# pca20054_sheet4_power_control.net
KiCad netlist of a schematic drawn in Altium Designer
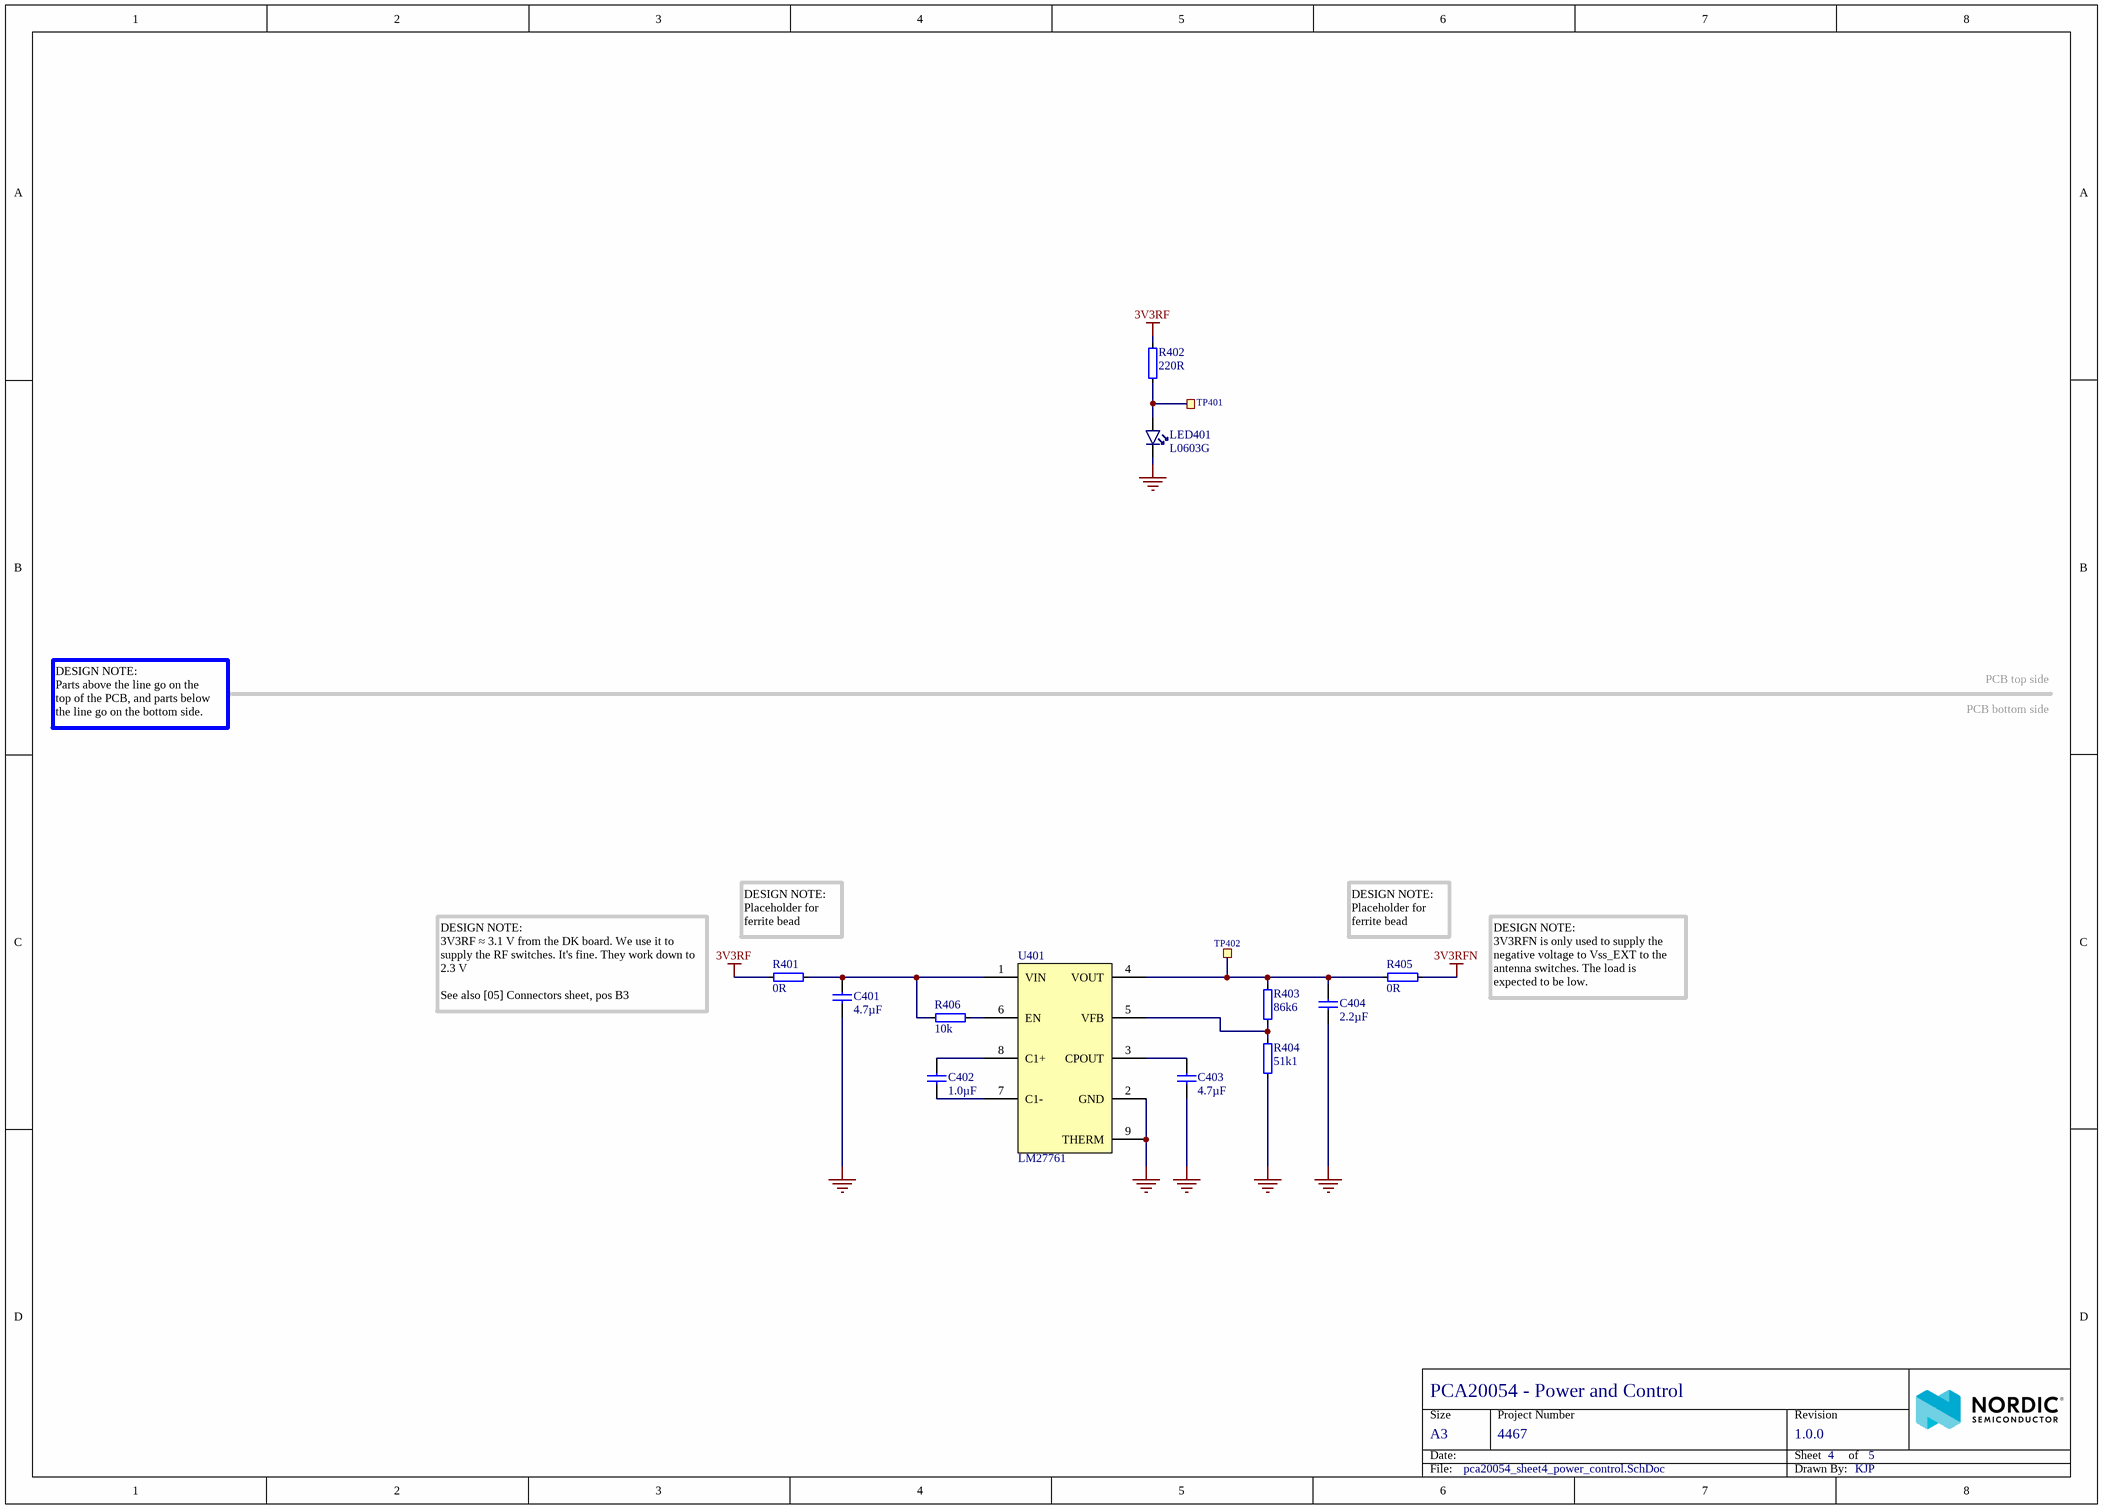
[diagram p0: pca20054_sheet4_power_control.SchDoc]

(export (version "E")
  (design (tool "Eeschema 10.0.6"))
  (components
    (comp (ref "C401")
      (value "4.7µF")
      (footprint "CAPC1608X06L")
      (description "Capacitor, X5R, ±10%")
      (fields (field (name "PART NUMBER") "C0603-4µ7") (field (name "PUBLISHER") "Nordic Semiconductor"))
      (libsource (lib "Nordic Passive DB") (part "CAP"))
    )
    (comp (ref "C402")
      (value "1.0µF")
      (footprint "CAPC1608X06L")
      (description "Capacitor, X7R, ±10%")
      (fields (field (name "PART NUMBER") "C0603-1µ0") (field (name "PUBLISHER") "Nordic Semiconductor"))
      (libsource (lib "Nordic Passive DB") (part "CAP"))
    )
    (comp (ref "C403")
      (value "4.7µF")
      (footprint "CAPC1608X06L")
      (description "Capacitor, X5R, ±10%")
      (fields (field (name "PART NUMBER") "C0603-4µ7") (field (name "PUBLISHER") "Nordic Semiconductor"))
      (libsource (lib "Nordic Passive DB") (part "CAP"))
    )
    (comp (ref "C404")
      (value "2.2µF")
      (footprint "CAPC1608X06L")
      (description "Capacitor, X7R, ±10%")
      (fields (field (name "PART NUMBER") "C0603-2µ2") (field (name "PUBLISHER") "Nordic Semiconductor"))
      (libsource (lib "Nordic Passive DB") (part "CAP"))
    )
    (comp (ref "LED401")
      (value "L0603G")
      (footprint "LED_0603_G")
      (description "LED, Green, 0603, 570nm, Vf=1.7V, 2.24..5.6mcd, - 40 to +100°C")
      (fields
        (field (name "PART NUMBER") "LG L29K Smartled Green")
        (field (name "MANUFACTURER") "Osram")
        (field (name "PUBLISHER") "Nordic Semiconductor")
      )
      (libsource (lib "Nordic Discrete DB") (part "D{colon}LED"))
    )
    (comp (ref "R401")
      (value "0R")
      (footprint "RESC1005X04L")
      (description "Resistor, ±5%, 0.063W")
      (fields (field (name "PART NUMBER") "R0402-0R") (field (name "PUBLISHER") "Nordic Semiconductor"))
      (libsource (lib "Nordic Passive DB") (part "RES"))
    )
    (comp (ref "R402")
      (value "220R")
      (footprint "RESC1005X04L")
      (description "Resistor, ±1%, 0.063W")
      (fields (field (name "PART NUMBER") "R0402-220") (field (name "PUBLISHER") "Nordic Semiconductor"))
      (libsource (lib "Nordic Passive DB") (part "RES"))
    )
    (comp (ref "R403")
      (value "86k6")
      (footprint "RESC1005X04L")
      (description "Resistor, ±1%, 0.063W")
      (fields
        (field (name "PART NUMBER") "R0402-86k6")
        (field (name "MANUFACTURER") "Panasonic")
        (field (name "PUBLISHER") "Nordic Semiconductor")
      )
      (libsource (lib "Nordic Passive DB") (part "RES"))
    )
    (comp (ref "R404")
      (value "51k1")
      (footprint "RESC1005X04L")
      (description "Resistor, ±0.1%, 0.063W")
      (fields
        (field (name "PART NUMBER") "R0402-51k1")
        (field (name "MANUFACTURER") "Panasonic")
        (field (name "PUBLISHER") "Nordic Semiconductor")
      )
      (libsource (lib "Nordic Passive DB") (part "RES"))
    )
    (comp (ref "R405")
      (value "0R")
      (footprint "RESC1005X04L")
      (description "Resistor, ±5%, 0.063W")
      (fields (field (name "PART NUMBER") "R0402-0R") (field (name "PUBLISHER") "Nordic Semiconductor"))
      (libsource (lib "Nordic Passive DB") (part "RES"))
    )
    (comp (ref "R406")
      (value "10k")
      (footprint "RESC1005X04L")
      (description "Resistor, ±1%, 0.063W")
      (fields (field (name "PART NUMBER") "R0402-10k") (field (name "PUBLISHER") "Nordic Semiconductor"))
      (libsource (lib "Nordic Passive DB") (part "RES"))
    )
    (comp (ref "TP401")
      (value "Ø1.0mm,SMD")
      (footprint "TP_SMD_?.0mm")
      (description "1.0mm circular SMD testpad")
      (fields
        (field (name "PART NUMBER") "TP_SMD_Ø1.0MM")
        (field (name "MANUFACTURER") "Nordic Semiconductor")
        (field (name "PUBLISHER") "Nordic Semiconductor")
      )
      (libsource (lib "Nordic Passive DB") (part "TESTPAD"))
    )
    (comp (ref "TP402")
      (value "Ø1.0mm,SMD")
      (footprint "TP_SMD_?.0mm")
      (description "1.0mm circular SMD testpad")
      (fields
        (field (name "PART NUMBER") "TP_SMD_Ø1.0MM")
        (field (name "MANUFACTURER") "Nordic Semiconductor")
        (field (name "PUBLISHER") "Nordic Semiconductor")
      )
      (libsource (lib "") (part "TESTPAD_1"))
    )
    (comp (ref "U401")
      (value "LM27761")
      (footprint "SON50P200X80_HS-9L")
      (description "Low-Noise, Regulated, Switched-Capacitor Voltage Inverter")
      (fields
        (field (name "MANUFACTURER") "Texas Instruments")
        (field (name "PUBLISHER") "Nordic Semiconductor")
      )
      (libsource (lib "Nordic Active DB") (part "LM27761"))
    )
  )
  (nets
    (net (code "1") (name "3V3RF") (class "Default")
      (node (ref "R401") (pin "1") (pinfunction "1_1") (pintype "passive"))
      (node (ref "R402") (pin "2") (pinfunction "2_2") (pintype "passive"))
    )
    (net (code "2") (name "3V3RFN") (class "Default")
      (node (ref "R405") (pin "2") (pinfunction "2_2") (pintype "passive"))
    )
    (net (code "3") (name "GND") (class "Default")
      (node (ref "C401") (pin "1") (pinfunction "1_1") (pintype "passive"))
      (node (ref "C403") (pin "1") (pinfunction "1_1") (pintype "passive"))
      (node (ref "C404") (pin "1") (pinfunction "1_1") (pintype "passive"))
      (node (ref "LED401") (pin "1") (pinfunction "C_1") (pintype "passive"))
      (node (ref "R404") (pin "1") (pinfunction "1_1") (pintype "passive"))
      (node (ref "U401") (pin "2") (pinfunction "GND_2") (pintype "power_in"))
      (node (ref "U401") (pin "9") (pinfunction "THERM_9") (pintype "power_in"))
    )
    (net (code "4") (name "Net-(LED401-A)") (class "Default")
      (node (ref "LED401") (pin "2") (pinfunction "A_2") (pintype "passive"))
      (node (ref "R402") (pin "1") (pinfunction "1_1") (pintype "passive"))
      (node (ref "TP401") (pin "1") (pinfunction "1_1") (pintype "passive"))
    )
    (net (code "5") (name "Net-(U401-C1+)") (class "Default")
      (node (ref "C402") (pin "2") (pinfunction "2_2") (pintype "passive"))
      (node (ref "U401") (pin "8") (pinfunction "C1+_8") (pintype "power_in"))
    )
    (net (code "6") (name "Net-(U401-C1-)") (class "Default")
      (node (ref "C402") (pin "1") (pinfunction "1_1") (pintype "passive"))
      (node (ref "U401") (pin "7") (pinfunction "C1-_7") (pintype "power_in"))
    )
    (net (code "7") (name "Net-(U401-CPOUT)") (class "Default")
      (node (ref "C403") (pin "2") (pinfunction "2_2") (pintype "passive"))
      (node (ref "U401") (pin "3") (pinfunction "CPOUT_3") (pintype "power_in"))
    )
    (net (code "8") (name "Net-(U401-EN)") (class "Default")
      (node (ref "R406") (pin "2") (pinfunction "2_2") (pintype "passive"))
      (node (ref "U401") (pin "6") (pinfunction "EN_6") (pintype "passive"))
    )
    (net (code "9") (name "Net-(U401-VFB)") (class "Default")
      (node (ref "R403") (pin "1") (pinfunction "1_1") (pintype "passive"))
      (node (ref "R404") (pin "2") (pinfunction "2_2") (pintype "passive"))
      (node (ref "U401") (pin "5") (pinfunction "VFB_5") (pintype "power_in"))
    )
    (net (code "10") (name "Net-(U401-VIN)") (class "Default")
      (node (ref "C401") (pin "2") (pinfunction "2_2") (pintype "passive"))
      (node (ref "R401") (pin "2") (pinfunction "2_2") (pintype "passive"))
      (node (ref "R406") (pin "1") (pinfunction "1_1") (pintype "passive"))
      (node (ref "U401") (pin "1") (pinfunction "VIN_1") (pintype "power_in"))
    )
    (net (code "11") (name "Net-(U401-VOUT)") (class "Default")
      (node (ref "C404") (pin "2") (pinfunction "2_2") (pintype "passive"))
      (node (ref "R403") (pin "2") (pinfunction "2_2") (pintype "passive"))
      (node (ref "R405") (pin "1") (pinfunction "1_1") (pintype "passive"))
      (node (ref "TP402") (pin "1") (pinfunction "1_1") (pintype "passive"))
      (node (ref "U401") (pin "4") (pinfunction "VOUT_4") (pintype "power_in"))
    )
  )
)
